# untitled.net
KiCad netlist of a schematic drawn in EAGLE
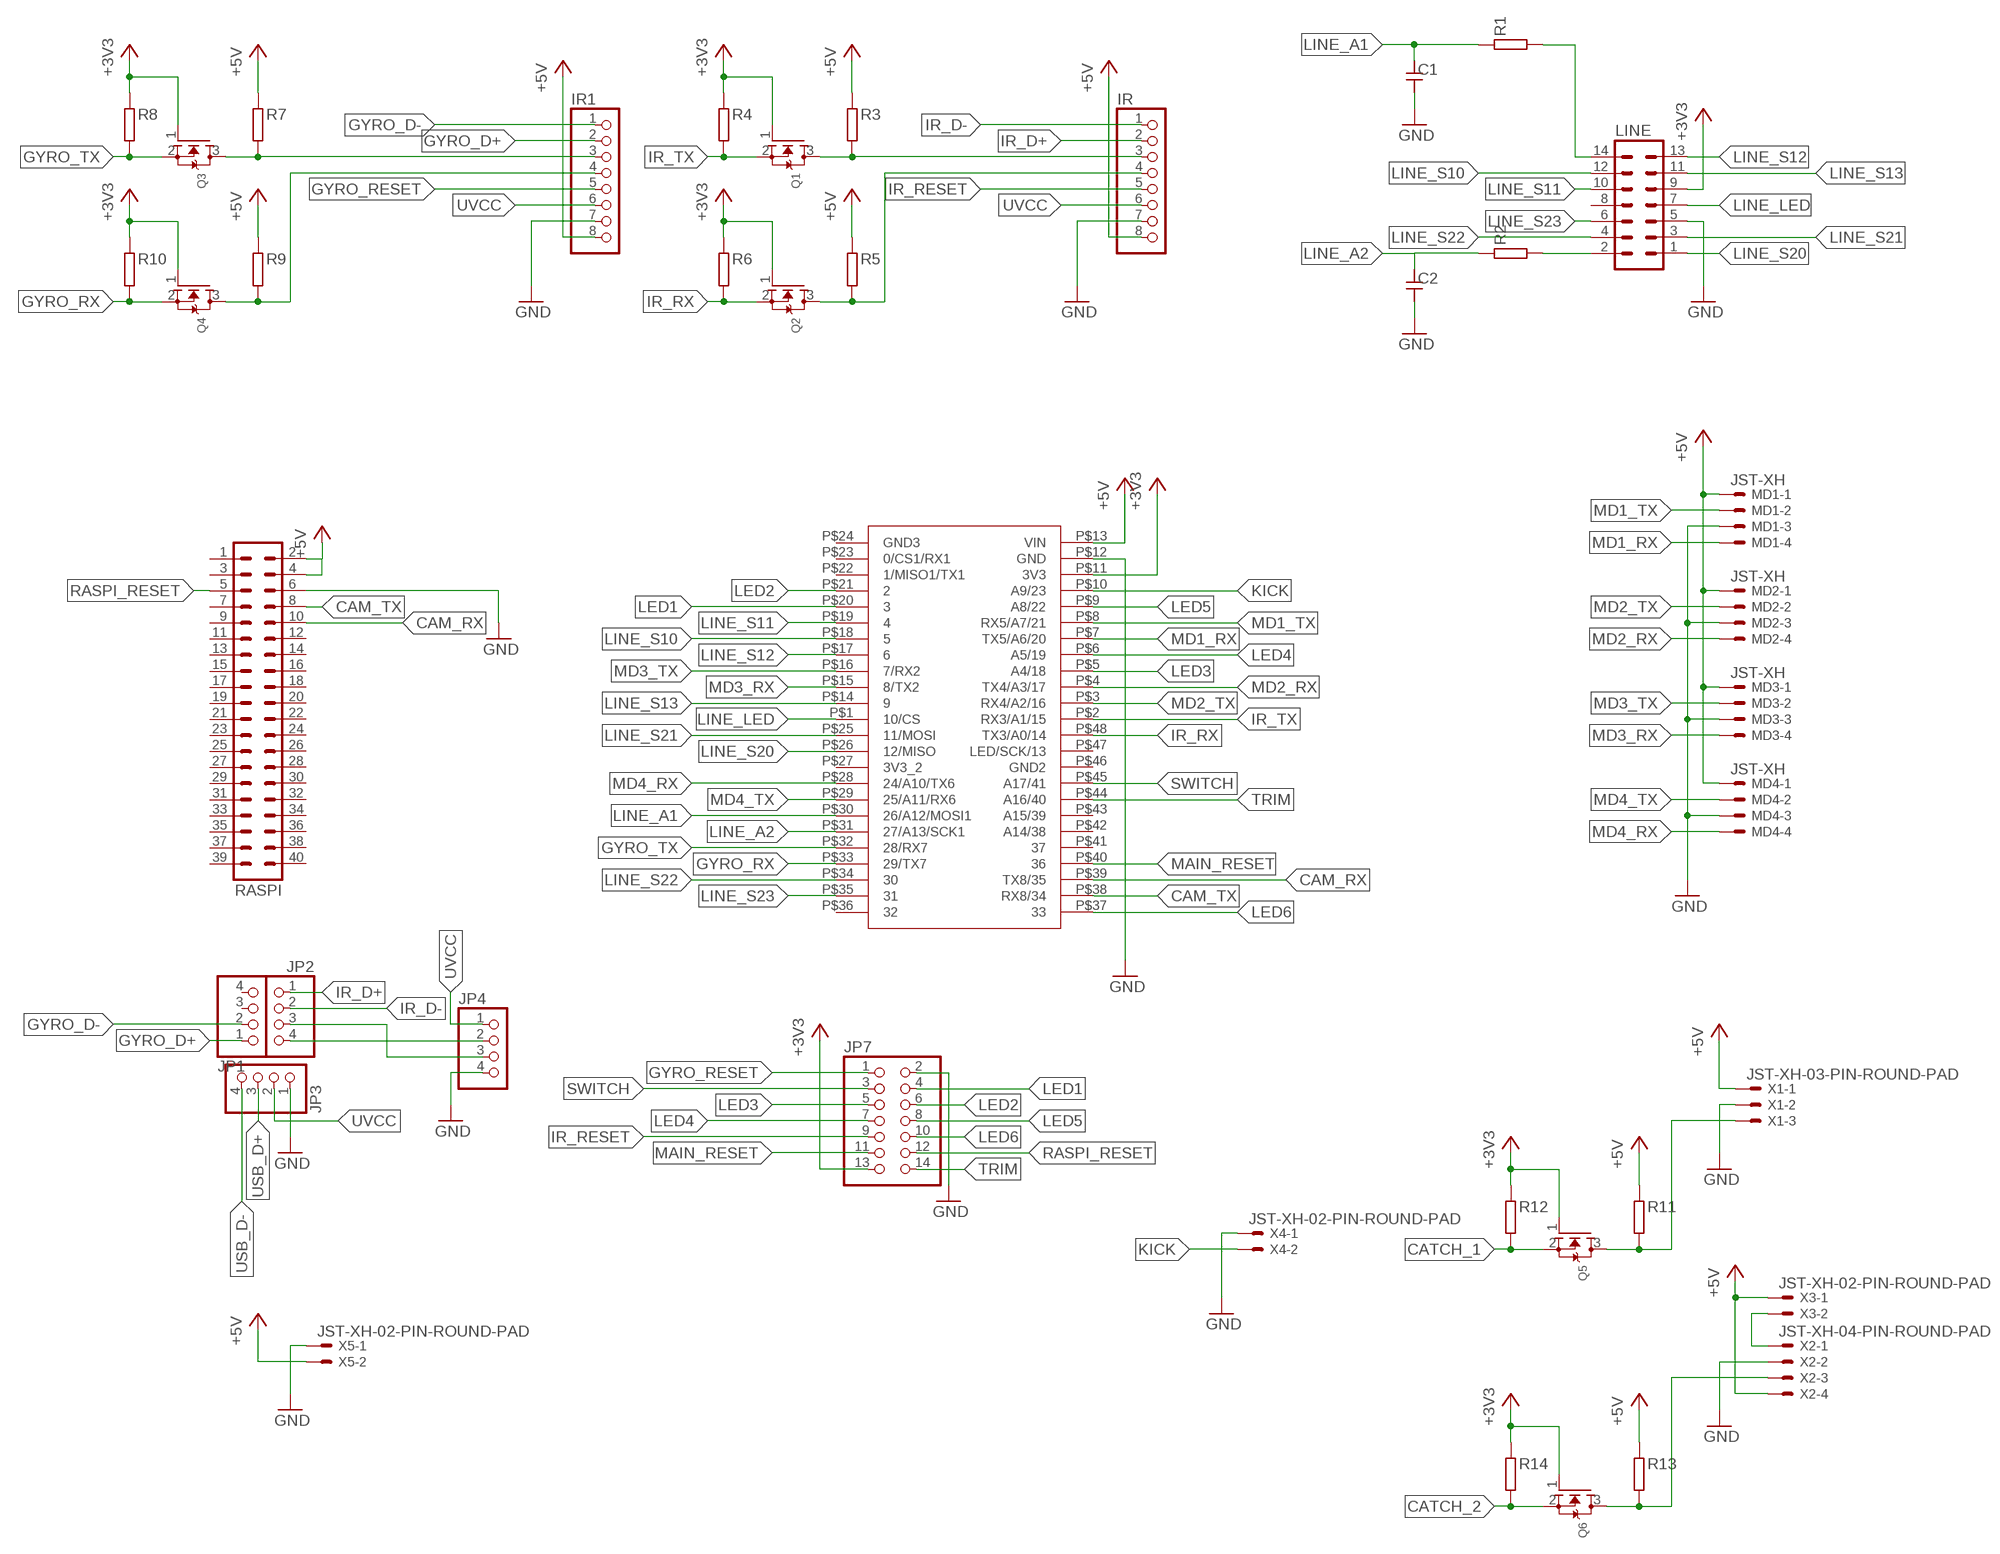
[diagram p0: schematic, sheet 1]

(export (version "E")
  (design (tool "Eeschema 10.0.6"))
  (components
    (comp (ref "C1")
      (value "CAPACITOR1608")
      (footprint "eagle-import:SMD1608")
      (libsource (lib "eagle-import") (part "CAPACITOR1608"))
    )
    (comp (ref "C2")
      (value "CAPACITOR1608")
      (footprint "eagle-import:SMD1608")
      (libsource (lib "eagle-import") (part "CAPACITOR1608"))
    )
    (comp (ref "IR")
      (value "PINHD-1X8")
      (footprint "eagle-import:1X08")
      (libsource (lib "eagle-import") (part "PINHD-1X8"))
    )
    (comp (ref "IR1")
      (value "PINHD-1X8")
      (footprint "eagle-import:1X08")
      (libsource (lib "eagle-import") (part "PINHD-1X8"))
    )
    (comp (ref "JP1")
      (value "PINHD-1X4")
      (footprint "eagle-import:1X04")
      (libsource (lib "eagle-import") (part "PINHD-1X4"))
    )
    (comp (ref "JP2")
      (value "PINHD-1X4")
      (footprint "eagle-import:1X04")
      (libsource (lib "eagle-import") (part "PINHD-1X4"))
    )
    (comp (ref "JP3")
      (value "PINHD-1X4")
      (footprint "eagle-import:1X04")
      (libsource (lib "eagle-import") (part "PINHD-1X4"))
    )
    (comp (ref "JP4")
      (value "PINHD-1X4")
      (footprint "eagle-import:1X04")
      (libsource (lib "eagle-import") (part "PINHD-1X4"))
    )
    (comp (ref "JP7")
      (value "PINHD-2X7")
      (footprint "eagle-import:2X07")
      (libsource (lib "eagle-import") (part "PINHD-2X7"))
    )
    (comp (ref "LINE")
      (value "MA07-2")
      (footprint "eagle-import:MA07-2")
      (libsource (lib "eagle-import") (part "MA07-2"))
    )
    (comp (ref "MD1")
      (value "JST-XH")
      (footprint "eagle-import:JST-XH-04-PACKAGE-ROUND-PAD")
      (libsource (lib "eagle-import") (part "JST-XH-04-PIN-ROUND-PAD"))
    )
    (comp (ref "MD2")
      (value "JST-XH")
      (footprint "eagle-import:JST-XH-04-PACKAGE-ROUND-PAD")
      (libsource (lib "eagle-import") (part "JST-XH-04-PIN-ROUND-PAD"))
    )
    (comp (ref "MD3")
      (value "JST-XH")
      (footprint "eagle-import:JST-XH-04-PACKAGE-ROUND-PAD")
      (libsource (lib "eagle-import") (part "JST-XH-04-PIN-ROUND-PAD"))
    )
    (comp (ref "MD4")
      (value "JST-XH")
      (footprint "eagle-import:JST-XH-04-PACKAGE-ROUND-PAD")
      (libsource (lib "eagle-import") (part "JST-XH-04-PIN-ROUND-PAD"))
    )
    (comp (ref "Q1")
      (value "MOSFET-NREFLOW")
      (footprint "eagle-import:SOT23")
      (libsource (lib "eagle-import") (part "MOSFET-NREFLOW"))
    )
    (comp (ref "Q2")
      (value "MOSFET-NREFLOW")
      (footprint "eagle-import:SOT23")
      (libsource (lib "eagle-import") (part "MOSFET-NREFLOW"))
    )
    (comp (ref "Q3")
      (value "MOSFET-NREFLOW")
      (footprint "eagle-import:SOT23")
      (libsource (lib "eagle-import") (part "MOSFET-NREFLOW"))
    )
    (comp (ref "Q4")
      (value "MOSFET-NREFLOW")
      (footprint "eagle-import:SOT23")
      (libsource (lib "eagle-import") (part "MOSFET-NREFLOW"))
    )
    (comp (ref "Q5")
      (value "MOSFET-NREFLOW")
      (footprint "eagle-import:SOT23")
      (libsource (lib "eagle-import") (part "MOSFET-NREFLOW"))
    )
    (comp (ref "Q6")
      (value "MOSFET-NREFLOW")
      (footprint "eagle-import:SOT23")
      (libsource (lib "eagle-import") (part "MOSFET-NREFLOW"))
    )
    (comp (ref "R1")
      (value "RESISTOR1608")
      (footprint "eagle-import:SMD1608")
      (libsource (lib "eagle-import") (part "RESISTOR1608"))
    )
    (comp (ref "R2")
      (value "RESISTOR1608")
      (footprint "eagle-import:SMD1608")
      (libsource (lib "eagle-import") (part "RESISTOR1608"))
    )
    (comp (ref "R3")
      (value "RESISTOR1608")
      (footprint "eagle-import:SMD1608")
      (libsource (lib "eagle-import") (part "RESISTOR1608"))
    )
    (comp (ref "R4")
      (value "RESISTOR1608")
      (footprint "eagle-import:SMD1608")
      (libsource (lib "eagle-import") (part "RESISTOR1608"))
    )
    (comp (ref "R5")
      (value "RESISTOR1608")
      (footprint "eagle-import:SMD1608")
      (libsource (lib "eagle-import") (part "RESISTOR1608"))
    )
    (comp (ref "R6")
      (value "RESISTOR1608")
      (footprint "eagle-import:SMD1608")
      (libsource (lib "eagle-import") (part "RESISTOR1608"))
    )
    (comp (ref "R7")
      (value "RESISTOR1608")
      (footprint "eagle-import:SMD1608")
      (libsource (lib "eagle-import") (part "RESISTOR1608"))
    )
    (comp (ref "R8")
      (value "RESISTOR1608")
      (footprint "eagle-import:SMD1608")
      (libsource (lib "eagle-import") (part "RESISTOR1608"))
    )
    (comp (ref "R9")
      (value "RESISTOR1608")
      (footprint "eagle-import:SMD1608")
      (libsource (lib "eagle-import") (part "RESISTOR1608"))
    )
    (comp (ref "R10")
      (value "RESISTOR1608")
      (footprint "eagle-import:SMD1608")
      (libsource (lib "eagle-import") (part "RESISTOR1608"))
    )
    (comp (ref "R11")
      (value "RESISTOR1608")
      (footprint "eagle-import:SMD1608")
      (libsource (lib "eagle-import") (part "RESISTOR1608"))
    )
    (comp (ref "R12")
      (value "RESISTOR1608")
      (footprint "eagle-import:SMD1608")
      (libsource (lib "eagle-import") (part "RESISTOR1608"))
    )
    (comp (ref "R13")
      (value "RESISTOR1608")
      (footprint "eagle-import:SMD1608")
      (libsource (lib "eagle-import") (part "RESISTOR1608"))
    )
    (comp (ref "R14")
      (value "RESISTOR1608")
      (footprint "eagle-import:SMD1608")
      (libsource (lib "eagle-import") (part "RESISTOR1608"))
    )
    (comp (ref "RASPI")
      (value "MA20-2")
      (footprint "eagle-import:MA20-2")
      (libsource (lib "eagle-import") (part "MA20-2"))
    )
    (comp (ref "U$1")
      (value "TEENSY4.1")
      (footprint "eagle-import:TEENSY4.1")
      (libsource (lib "eagle-import") (part "TEENSY4.1"))
    )
    (comp (ref "X1")
      (value "JST-XH-03-PIN-ROUND-PAD")
      (footprint "eagle-import:JST-XH-03-PACKAGE-ROUND-PAD")
      (libsource (lib "eagle-import") (part "JST-XH-03-PIN-ROUND-PAD"))
    )
    (comp (ref "X2")
      (value "JST-XH-04-PIN-ROUND-PAD")
      (footprint "eagle-import:JST-XH-04-PACKAGE-ROUND-PAD")
      (libsource (lib "eagle-import") (part "JST-XH-04-PIN-ROUND-PAD"))
    )
    (comp (ref "X3")
      (value "JST-XH-02-PIN-ROUND-PAD")
      (footprint "eagle-import:JST-XH-02-PACKAGE-ROUND-PAD")
      (libsource (lib "eagle-import") (part "JST-XH-02-PIN-ROUND-PAD"))
    )
    (comp (ref "X4")
      (value "JST-XH-02-PIN-ROUND-PAD")
      (footprint "eagle-import:JST-XH-02-PACKAGE-ROUND-PAD")
      (libsource (lib "eagle-import") (part "JST-XH-02-PIN-ROUND-PAD"))
    )
    (comp (ref "X5")
      (value "JST-XH-02-PIN-ROUND-PAD")
      (footprint "eagle-import:JST-XH-02-PACKAGE-ROUND-PAD")
      (libsource (lib "eagle-import") (part "JST-XH-02-PIN-ROUND-PAD"))
    )
  )
  (nets
    (net (code "1") (name "+3V3") (class "Default")
      (node (ref "JP7") (pin "13") (pinfunction "13_13") (pintype "passive"))
      (node (ref "LINE") (pin "9") (pinfunction "9_9") (pintype "passive"))
      (node (ref "Q1") (pin "1") (pinfunction "G_1") (pintype "bidirectional"))
      (node (ref "Q2") (pin "1") (pinfunction "G_1") (pintype "bidirectional"))
      (node (ref "Q3") (pin "1") (pinfunction "G_1") (pintype "bidirectional"))
      (node (ref "Q4") (pin "1") (pinfunction "G_1") (pintype "bidirectional"))
      (node (ref "Q5") (pin "1") (pinfunction "G_1") (pintype "bidirectional"))
      (node (ref "Q6") (pin "1") (pinfunction "G_1") (pintype "bidirectional"))
      (node (ref "R10") (pin "1") (pinfunction "1_1") (pintype "passive"))
      (node (ref "R12") (pin "1") (pinfunction "1_1") (pintype "passive"))
      (node (ref "R14") (pin "1") (pinfunction "1_1") (pintype "passive"))
      (node (ref "R4") (pin "1") (pinfunction "1_1") (pintype "passive"))
      (node (ref "R6") (pin "1") (pinfunction "1_1") (pintype "passive"))
      (node (ref "R8") (pin "1") (pinfunction "1_1") (pintype "passive"))
      (node (ref "U$1") (pin "P$11") (pinfunction "3V3_P$11") (pintype "bidirectional"))
    )
    (net (code "2") (name "+5V") (class "Default")
      (node (ref "IR") (pin "8") (pinfunction "8_8") (pintype "passive"))
      (node (ref "IR1") (pin "8") (pinfunction "8_8") (pintype "passive"))
      (node (ref "MD1") (pin "1") (pinfunction "S_1") (pintype "passive"))
      (node (ref "MD2") (pin "1") (pinfunction "S_1") (pintype "passive"))
      (node (ref "MD3") (pin "1") (pinfunction "S_1") (pintype "passive"))
      (node (ref "MD4") (pin "1") (pinfunction "S_1") (pintype "passive"))
      (node (ref "R11") (pin "1") (pinfunction "1_1") (pintype "passive"))
      (node (ref "R13") (pin "1") (pinfunction "1_1") (pintype "passive"))
      (node (ref "R3") (pin "1") (pinfunction "1_1") (pintype "passive"))
      (node (ref "R5") (pin "1") (pinfunction "1_1") (pintype "passive"))
      (node (ref "R7") (pin "1") (pinfunction "1_1") (pintype "passive"))
      (node (ref "R9") (pin "1") (pinfunction "1_1") (pintype "passive"))
      (node (ref "RASPI") (pin "2") (pinfunction "2_2") (pintype "passive"))
      (node (ref "RASPI") (pin "4") (pinfunction "4_4") (pintype "passive"))
      (node (ref "U$1") (pin "P$13") (pinfunction "VIN_P$13") (pintype "bidirectional"))
      (node (ref "X1") (pin "1") (pinfunction "S_1") (pintype "passive"))
      (node (ref "X2") (pin "4") (pinfunction "S_4") (pintype "passive"))
      (node (ref "X3") (pin "1") (pinfunction "S_1") (pintype "passive"))
      (node (ref "X5") (pin "2") (pinfunction "S_2") (pintype "passive"))
    )
    (net (code "3") (name "CAM_RX") (class "Default")
      (node (ref "RASPI") (pin "10") (pinfunction "10_10") (pintype "passive"))
      (node (ref "U$1") (pin "P$39") (pinfunction "TX8/35_P$39") (pintype "bidirectional"))
    )
    (net (code "4") (name "CAM_TX") (class "Default")
      (node (ref "RASPI") (pin "8") (pinfunction "8_8") (pintype "passive"))
      (node (ref "U$1") (pin "P$38") (pinfunction "RX8/34_P$38") (pintype "bidirectional"))
    )
    (net (code "5") (name "CATCH_1") (class "Default")
      (node (ref "Q5") (pin "2") (pinfunction "S_2") (pintype "bidirectional"))
      (node (ref "R12") (pin "2") (pinfunction "2_2") (pintype "passive"))
    )
    (net (code "6") (name "CATCH_2") (class "Default")
      (node (ref "Q6") (pin "2") (pinfunction "S_2") (pintype "bidirectional"))
      (node (ref "R14") (pin "2") (pinfunction "2_2") (pintype "passive"))
    )
    (net (code "7") (name "GND") (class "Default")
      (node (ref "C1") (pin "2") (pinfunction "2_2") (pintype "passive"))
      (node (ref "C2") (pin "2") (pinfunction "2_2") (pintype "passive"))
      (node (ref "IR") (pin "7") (pinfunction "7_7") (pintype "passive"))
      (node (ref "IR1") (pin "7") (pinfunction "7_7") (pintype "passive"))
      (node (ref "JP3") (pin "1") (pinfunction "1_1") (pintype "passive"))
      (node (ref "JP4") (pin "4") (pinfunction "4_4") (pintype "passive"))
      (node (ref "JP7") (pin "2") (pinfunction "2_2") (pintype "passive"))
      (node (ref "LINE") (pin "5") (pinfunction "5_5") (pintype "passive"))
      (node (ref "MD1") (pin "3") (pinfunction "S_3") (pintype "passive"))
      (node (ref "MD2") (pin "3") (pinfunction "S_3") (pintype "passive"))
      (node (ref "MD3") (pin "3") (pinfunction "S_3") (pintype "passive"))
      (node (ref "MD4") (pin "3") (pinfunction "S_3") (pintype "passive"))
      (node (ref "RASPI") (pin "6") (pinfunction "6_6") (pintype "passive"))
      (node (ref "U$1") (pin "P$12") (pinfunction "GND_P$12") (pintype "bidirectional"))
      (node (ref "X1") (pin "2") (pinfunction "S_2") (pintype "passive"))
      (node (ref "X2") (pin "2") (pinfunction "S_2") (pintype "passive"))
      (node (ref "X4") (pin "1") (pinfunction "S_1") (pintype "passive"))
      (node (ref "X5") (pin "1") (pinfunction "S_1") (pintype "passive"))
    )
    (net (code "8") (name "GYRO_D+") (class "Default")
      (node (ref "IR1") (pin "2") (pinfunction "2_2") (pintype "passive"))
      (node (ref "JP1") (pin "1") (pinfunction "1_1") (pintype "passive"))
    )
    (net (code "9") (name "GYRO_D-") (class "Default")
      (node (ref "IR1") (pin "1") (pinfunction "1_1") (pintype "passive"))
      (node (ref "JP1") (pin "2") (pinfunction "2_2") (pintype "passive"))
    )
    (net (code "10") (name "GYRO_RESET") (class "Default")
      (node (ref "IR1") (pin "5") (pinfunction "5_5") (pintype "passive"))
      (node (ref "JP7") (pin "1") (pinfunction "1_1") (pintype "passive"))
    )
    (net (code "11") (name "GYRO_RX") (class "Default")
      (node (ref "Q4") (pin "2") (pinfunction "S_2") (pintype "bidirectional"))
      (node (ref "R10") (pin "2") (pinfunction "2_2") (pintype "passive"))
      (node (ref "U$1") (pin "P$33") (pinfunction "29/TX7_P$33") (pintype "bidirectional"))
    )
    (net (code "12") (name "GYRO_TX") (class "Default")
      (node (ref "Q3") (pin "2") (pinfunction "S_2") (pintype "bidirectional"))
      (node (ref "R8") (pin "2") (pinfunction "2_2") (pintype "passive"))
      (node (ref "U$1") (pin "P$32") (pinfunction "28/RX7_P$32") (pintype "bidirectional"))
    )
    (net (code "13") (name "IR_D+") (class "Default")
      (node (ref "IR") (pin "2") (pinfunction "2_2") (pintype "passive"))
      (node (ref "JP2") (pin "1") (pinfunction "1_1") (pintype "passive"))
    )
    (net (code "14") (name "IR_D-") (class "Default")
      (node (ref "IR") (pin "1") (pinfunction "1_1") (pintype "passive"))
      (node (ref "JP2") (pin "2") (pinfunction "2_2") (pintype "passive"))
    )
    (net (code "15") (name "IR_RESET") (class "Default")
      (node (ref "IR") (pin "5") (pinfunction "5_5") (pintype "passive"))
      (node (ref "JP7") (pin "9") (pinfunction "9_9") (pintype "passive"))
    )
    (net (code "16") (name "IR_RX") (class "Default")
      (node (ref "Q2") (pin "2") (pinfunction "S_2") (pintype "bidirectional"))
      (node (ref "R6") (pin "2") (pinfunction "2_2") (pintype "passive"))
      (node (ref "U$1") (pin "P$48") (pinfunction "TX3/A0/14_P$48") (pintype "bidirectional"))
    )
    (net (code "17") (name "IR_TX") (class "Default")
      (node (ref "Q1") (pin "2") (pinfunction "S_2") (pintype "bidirectional"))
      (node (ref "R4") (pin "2") (pinfunction "2_2") (pintype "passive"))
      (node (ref "U$1") (pin "P$2") (pinfunction "RX3/A1/15_P$2") (pintype "bidirectional"))
    )
    (net (code "18") (name "KICK") (class "Default")
      (node (ref "U$1") (pin "P$10") (pinfunction "A9/23_P$10") (pintype "bidirectional"))
      (node (ref "X4") (pin "2") (pinfunction "S_2") (pintype "passive"))
    )
    (net (code "19") (name "LED1") (class "Default")
      (node (ref "JP7") (pin "4") (pinfunction "4_4") (pintype "passive"))
      (node (ref "U$1") (pin "P$20") (pinfunction "3_P$20") (pintype "bidirectional"))
    )
    (net (code "20") (name "LED2") (class "Default")
      (node (ref "JP7") (pin "6") (pinfunction "6_6") (pintype "passive"))
      (node (ref "U$1") (pin "P$21") (pinfunction "2_P$21") (pintype "bidirectional"))
    )
    (net (code "21") (name "LED3") (class "Default")
      (node (ref "JP7") (pin "5") (pinfunction "5_5") (pintype "passive"))
      (node (ref "U$1") (pin "P$5") (pinfunction "A4/18_P$5") (pintype "bidirectional"))
    )
    (net (code "22") (name "LED4") (class "Default")
      (node (ref "JP7") (pin "7") (pinfunction "7_7") (pintype "passive"))
      (node (ref "U$1") (pin "P$6") (pinfunction "A5/19_P$6") (pintype "bidirectional"))
    )
    (net (code "23") (name "LED5") (class "Default")
      (node (ref "JP7") (pin "8") (pinfunction "8_8") (pintype "passive"))
      (node (ref "U$1") (pin "P$9") (pinfunction "A8/22_P$9") (pintype "bidirectional"))
    )
    (net (code "24") (name "LED6") (class "Default")
      (node (ref "JP7") (pin "10") (pinfunction "10_10") (pintype "passive"))
      (node (ref "U$1") (pin "P$37") (pinfunction "33_P$37") (pintype "bidirectional"))
    )
    (net (code "25") (name "LINE_A1") (class "Default")
      (node (ref "C1") (pin "1") (pinfunction "1_1") (pintype "passive"))
      (node (ref "R1") (pin "1") (pinfunction "1_1") (pintype "passive"))
      (node (ref "U$1") (pin "P$30") (pinfunction "26/A12/MOSI1_P$30") (pintype "bidirectional"))
    )
    (net (code "26") (name "LINE_A2") (class "Default")
      (node (ref "C2") (pin "1") (pinfunction "1_1") (pintype "passive"))
      (node (ref "R2") (pin "1") (pinfunction "1_1") (pintype "passive"))
      (node (ref "U$1") (pin "P$31") (pinfunction "27/A13/SCK1_P$31") (pintype "bidirectional"))
    )
    (net (code "27") (name "LINE_LED") (class "Default")
      (node (ref "LINE") (pin "7") (pinfunction "7_7") (pintype "passive"))
      (node (ref "U$1") (pin "P$1") (pinfunction "10/CS_P$1") (pintype "bidirectional"))
    )
    (net (code "28") (name "LINE_S10") (class "Default")
      (node (ref "LINE") (pin "12") (pinfunction "12_12") (pintype "passive"))
      (node (ref "U$1") (pin "P$18") (pinfunction "5_P$18") (pintype "bidirectional"))
    )
    (net (code "29") (name "LINE_S11") (class "Default")
      (node (ref "LINE") (pin "10") (pinfunction "10_10") (pintype "passive"))
      (node (ref "U$1") (pin "P$19") (pinfunction "4_P$19") (pintype "bidirectional"))
    )
    (net (code "30") (name "LINE_S12") (class "Default")
      (node (ref "LINE") (pin "13") (pinfunction "13_13") (pintype "passive"))
      (node (ref "U$1") (pin "P$17") (pinfunction "6_P$17") (pintype "bidirectional"))
    )
    (net (code "31") (name "LINE_S13") (class "Default")
      (node (ref "LINE") (pin "11") (pinfunction "11_11") (pintype "passive"))
      (node (ref "U$1") (pin "P$14") (pinfunction "9_P$14") (pintype "bidirectional"))
    )
    (net (code "32") (name "LINE_S20") (class "Default")
      (node (ref "LINE") (pin "1") (pinfunction "1_1") (pintype "passive"))
      (node (ref "U$1") (pin "P$26") (pinfunction "12/MISO_P$26") (pintype "bidirectional"))
    )
    (net (code "33") (name "LINE_S21") (class "Default")
      (node (ref "LINE") (pin "3") (pinfunction "3_3") (pintype "passive"))
      (node (ref "U$1") (pin "P$25") (pinfunction "11/MOSI_P$25") (pintype "bidirectional"))
    )
    (net (code "34") (name "LINE_S22") (class "Default")
      (node (ref "LINE") (pin "4") (pinfunction "4_4") (pintype "passive"))
      (node (ref "U$1") (pin "P$34") (pinfunction "30_P$34") (pintype "bidirectional"))
    )
    (net (code "35") (name "LINE_S23") (class "Default")
      (node (ref "LINE") (pin "6") (pinfunction "6_6") (pintype "passive"))
      (node (ref "U$1") (pin "P$35") (pinfunction "31_P$35") (pintype "bidirectional"))
    )
    (net (code "36") (name "MAIN_RESET") (class "Default")
      (node (ref "JP7") (pin "11") (pinfunction "11_11") (pintype "passive"))
      (node (ref "U$1") (pin "P$40") (pinfunction "36_P$40") (pintype "bidirectional"))
    )
    (net (code "37") (name "MD1_RX") (class "Default")
      (node (ref "MD1") (pin "4") (pinfunction "S_4") (pintype "passive"))
      (node (ref "U$1") (pin "P$7") (pinfunction "TX5/A6/20_P$7") (pintype "bidirectional"))
    )
    (net (code "38") (name "MD1_TX") (class "Default")
      (node (ref "MD1") (pin "2") (pinfunction "S_2") (pintype "passive"))
      (node (ref "U$1") (pin "P$8") (pinfunction "RX5/A7/21_P$8") (pintype "bidirectional"))
    )
    (net (code "39") (name "MD2_RX") (class "Default")
      (node (ref "MD2") (pin "4") (pinfunction "S_4") (pintype "passive"))
      (node (ref "U$1") (pin "P$4") (pinfunction "TX4/A3/17_P$4") (pintype "bidirectional"))
    )
    (net (code "40") (name "MD2_TX") (class "Default")
      (node (ref "MD2") (pin "2") (pinfunction "S_2") (pintype "passive"))
      (node (ref "U$1") (pin "P$3") (pinfunction "RX4/A2/16_P$3") (pintype "bidirectional"))
    )
    (net (code "41") (name "MD3_RX") (class "Default")
      (node (ref "MD3") (pin "4") (pinfunction "S_4") (pintype "passive"))
      (node (ref "U$1") (pin "P$15") (pinfunction "8/TX2_P$15") (pintype "bidirectional"))
    )
    (net (code "42") (name "MD3_TX") (class "Default")
      (node (ref "MD3") (pin "2") (pinfunction "S_2") (pintype "passive"))
      (node (ref "U$1") (pin "P$16") (pinfunction "7/RX2_P$16") (pintype "bidirectional"))
    )
    (net (code "43") (name "MD4_RX") (class "Default")
      (node (ref "MD4") (pin "4") (pinfunction "S_4") (pintype "passive"))
      (node (ref "U$1") (pin "P$28") (pinfunction "24/A10/TX6_P$28") (pintype "bidirectional"))
    )
    (net (code "44") (name "MD4_TX") (class "Default")
      (node (ref "MD4") (pin "2") (pinfunction "S_2") (pintype "passive"))
      (node (ref "U$1") (pin "P$29") (pinfunction "25/A11/RX6_P$29") (pintype "bidirectional"))
    )
    (net (code "45") (name "Net-(JP2-Pad3)") (class "Default")
      (node (ref "JP2") (pin "3") (pinfunction "3_3") (pintype "passive"))
      (node (ref "JP4") (pin "3") (pinfunction "3_3") (pintype "passive"))
    )
    (net (code "46") (name "Net-(JP2-Pad4)") (class "Default")
      (node (ref "JP2") (pin "4") (pinfunction "4_4") (pintype "passive"))
      (node (ref "JP4") (pin "2") (pinfunction "2_2") (pintype "passive"))
    )
    (net (code "47") (name "Net-(LINE-Pad2)") (class "Default")
      (node (ref "LINE") (pin "2") (pinfunction "2_2") (pintype "passive"))
      (node (ref "R2") (pin "2") (pinfunction "2_2") (pintype "passive"))
    )
    (net (code "48") (name "Net-(LINE-Pad14)") (class "Default")
      (node (ref "LINE") (pin "14") (pinfunction "14_14") (pintype "passive"))
      (node (ref "R1") (pin "2") (pinfunction "2_2") (pintype "passive"))
    )
    (net (code "49") (name "Net-(Q1-D)") (class "Default")
      (node (ref "IR") (pin "3") (pinfunction "3_3") (pintype "passive"))
      (node (ref "Q1") (pin "3") (pinfunction "D_3") (pintype "bidirectional"))
      (node (ref "R3") (pin "2") (pinfunction "2_2") (pintype "passive"))
    )
    (net (code "50") (name "Net-(Q2-D)") (class "Default")
      (node (ref "IR") (pin "4") (pinfunction "4_4") (pintype "passive"))
      (node (ref "Q2") (pin "3") (pinfunction "D_3") (pintype "bidirectional"))
      (node (ref "R5") (pin "2") (pinfunction "2_2") (pintype "passive"))
    )
    (net (code "51") (name "Net-(Q3-D)") (class "Default")
      (node (ref "IR1") (pin "3") (pinfunction "3_3") (pintype "passive"))
      (node (ref "Q3") (pin "3") (pinfunction "D_3") (pintype "bidirectional"))
      (node (ref "R7") (pin "2") (pinfunction "2_2") (pintype "passive"))
    )
    (net (code "52") (name "Net-(Q4-D)") (class "Default")
      (node (ref "IR1") (pin "4") (pinfunction "4_4") (pintype "passive"))
      (node (ref "Q4") (pin "3") (pinfunction "D_3") (pintype "bidirectional"))
      (node (ref "R9") (pin "2") (pinfunction "2_2") (pintype "passive"))
    )
    (net (code "53") (name "Net-(Q5-D)") (class "Default")
      (node (ref "Q5") (pin "3") (pinfunction "D_3") (pintype "bidirectional"))
      (node (ref "R11") (pin "2") (pinfunction "2_2") (pintype "passive"))
      (node (ref "X1") (pin "3") (pinfunction "S_3") (pintype "passive"))
    )
    (net (code "54") (name "Net-(Q6-D)") (class "Default")
      (node (ref "Q6") (pin "3") (pinfunction "D_3") (pintype "bidirectional"))
      (node (ref "R13") (pin "2") (pinfunction "2_2") (pintype "passive"))
      (node (ref "X2") (pin "3") (pinfunction "S_3") (pintype "passive"))
    )
    (net (code "55") (name "Net-(X2A-S)") (class "Default")
      (node (ref "X2") (pin "1") (pinfunction "S_1") (pintype "passive"))
      (node (ref "X3") (pin "2") (pinfunction "S_2") (pintype "passive"))
    )
    (net (code "56") (name "RASPI_RESET") (class "Default")
      (node (ref "JP7") (pin "12") (pinfunction "12_12") (pintype "passive"))
      (node (ref "RASPI") (pin "5") (pinfunction "5_5") (pintype "passive"))
    )
    (net (code "57") (name "SWITCH") (class "Default")
      (node (ref "JP7") (pin "3") (pinfunction "3_3") (pintype "passive"))
      (node (ref "U$1") (pin "P$45") (pinfunction "A17/41_P$45") (pintype "bidirectional"))
    )
    (net (code "58") (name "TRIM") (class "Default")
      (node (ref "JP7") (pin "14") (pinfunction "14_14") (pintype "passive"))
      (node (ref "U$1") (pin "P$44") (pinfunction "A16/40_P$44") (pintype "bidirectional"))
    )
    (net (code "59") (name "USB_D+") (class "Default")
      (node (ref "JP3") (pin "3") (pinfunction "3_3") (pintype "passive"))
    )
    (net (code "60") (name "USB_D-") (class "Default")
      (node (ref "JP3") (pin "4") (pinfunction "4_4") (pintype "passive"))
    )
    (net (code "61") (name "UVCC") (class "Default")
      (node (ref "IR") (pin "6") (pinfunction "6_6") (pintype "passive"))
      (node (ref "IR1") (pin "6") (pinfunction "6_6") (pintype "passive"))
      (node (ref "JP3") (pin "2") (pinfunction "2_2") (pintype "passive"))
      (node (ref "JP4") (pin "1") (pinfunction "1_1") (pintype "passive"))
    )
    (net (code "62") (name "unconnected-(JP1-Pad3)") (class "Default")
      (node (ref "JP1") (pin "3") (pinfunction "3_3") (pintype "passive"))
    )
    (net (code "63") (name "unconnected-(JP1-Pad4)") (class "Default")
      (node (ref "JP1") (pin "4") (pinfunction "4_4") (pintype "passive"))
    )
    (net (code "64") (name "unconnected-(LINE-Pad8)") (class "Default")
      (node (ref "LINE") (pin "8") (pinfunction "8_8") (pintype "passive"))
    )
    (net (code "65") (name "unconnected-(RASPI-Pad1)") (class "Default")
      (node (ref "RASPI") (pin "1") (pinfunction "1_1") (pintype "passive"))
    )
    (net (code "66") (name "unconnected-(RASPI-Pad3)") (class "Default")
      (node (ref "RASPI") (pin "3") (pinfunction "3_3") (pintype "passive"))
    )
    (net (code "67") (name "unconnected-(RASPI-Pad7)") (class "Default")
      (node (ref "RASPI") (pin "7") (pinfunction "7_7") (pintype "passive"))
    )
    (net (code "68") (name "unconnected-(RASPI-Pad9)") (class "Default")
      (node (ref "RASPI") (pin "9") (pinfunction "9_9") (pintype "passive"))
    )
    (net (code "69") (name "unconnected-(RASPI-Pad11)") (class "Default")
      (node (ref "RASPI") (pin "11") (pinfunction "11_11") (pintype "passive"))
    )
    (net (code "70") (name "unconnected-(RASPI-Pad12)") (class "Default")
      (node (ref "RASPI") (pin "12") (pinfunction "12_12") (pintype "passive"))
    )
    (net (code "71") (name "unconnected-(RASPI-Pad13)") (class "Default")
      (node (ref "RASPI") (pin "13") (pinfunction "13_13") (pintype "passive"))
    )
    (net (code "72") (name "unconnected-(RASPI-Pad14)") (class "Default")
      (node (ref "RASPI") (pin "14") (pinfunction "14_14") (pintype "passive"))
    )
    (net (code "73") (name "unconnected-(RASPI-Pad15)") (class "Default")
      (node (ref "RASPI") (pin "15") (pinfunction "15_15") (pintype "passive"))
    )
    (net (code "74") (name "unconnected-(RASPI-Pad16)") (class "Default")
      (node (ref "RASPI") (pin "16") (pinfunction "16_16") (pintype "passive"))
    )
    (net (code "75") (name "unconnected-(RASPI-Pad17)") (class "Default")
      (node (ref "RASPI") (pin "17") (pinfunction "17_17") (pintype "passive"))
    )
    (net (code "76") (name "unconnected-(RASPI-Pad18)") (class "Default")
      (node (ref "RASPI") (pin "18") (pinfunction "18_18") (pintype "passive"))
    )
    (net (code "77") (name "unconnected-(RASPI-Pad19)") (class "Default")
      (node (ref "RASPI") (pin "19") (pinfunction "19_19") (pintype "passive"))
    )
    (net (code "78") (name "unconnected-(RASPI-Pad20)") (class "Default")
      (node (ref "RASPI") (pin "20") (pinfunction "20_20") (pintype "passive"))
    )
    (net (code "79") (name "unconnected-(RASPI-Pad21)") (class "Default")
      (node (ref "RASPI") (pin "21") (pinfunction "21_21") (pintype "passive"))
    )
    (net (code "80") (name "unconnected-(RASPI-Pad22)") (class "Default")
      (node (ref "RASPI") (pin "22") (pinfunction "22_22") (pintype "passive"))
    )
    (net (code "81") (name "unconnected-(RASPI-Pad23)") (class "Default")
      (node (ref "RASPI") (pin "23") (pinfunction "23_23") (pintype "passive"))
    )
    (net (code "82") (name "unconnected-(RASPI-Pad24)") (class "Default")
      (node (ref "RASPI") (pin "24") (pinfunction "24_24") (pintype "passive"))
    )
    (net (code "83") (name "unconnected-(RASPI-Pad25)") (class "Default")
      (node (ref "RASPI") (pin "25") (pinfunction "25_25") (pintype "passive"))
    )
    (net (code "84") (name "unconnected-(RASPI-Pad26)") (class "Default")
      (node (ref "RASPI") (pin "26") (pinfunction "26_26") (pintype "passive"))
    )
    (net (code "85") (name "unconnected-(RASPI-Pad27)") (class "Default")
      (node (ref "RASPI") (pin "27") (pinfunction "27_27") (pintype "passive"))
    )
    (net (code "86") (name "unconnected-(RASPI-Pad28)") (class "Default")
      (node (ref "RASPI") (pin "28") (pinfunction "28_28") (pintype "passive"))
    )
    (net (code "87") (name "unconnected-(RASPI-Pad29)") (class "Default")
      (node (ref "RASPI") (pin "29") (pinfunction "29_29") (pintype "passive"))
    )
    (net (code "88") (name "unconnected-(RASPI-Pad30)") (class "Default")
      (node (ref "RASPI") (pin "30") (pinfunction "30_30") (pintype "passive"))
    )
    (net (code "89") (name "unconnected-(RASPI-Pad31)") (class "Default")
      (node (ref "RASPI") (pin "31") (pinfunction "31_31") (pintype "passive"))
    )
    (net (code "90") (name "unconnected-(RASPI-Pad32)") (class "Default")
      (node (ref "RASPI") (pin "32") (pinfunction "32_32") (pintype "passive"))
    )
    (net (code "91") (name "unconnected-(RASPI-Pad33)") (class "Default")
      (node (ref "RASPI") (pin "33") (pinfunction "33_33") (pintype "passive"))
    )
    (net (code "92") (name "unconnected-(RASPI-Pad34)") (class "Default")
      (node (ref "RASPI") (pin "34") (pinfunction "34_34") (pintype "passive"))
    )
    (net (code "93") (name "unconnected-(RASPI-Pad35)") (class "Default")
      (node (ref "RASPI") (pin "35") (pinfunction "35_35") (pintype "passive"))
    )
    (net (code "94") (name "unconnected-(RASPI-Pad36)") (class "Default")
      (node (ref "RASPI") (pin "36") (pinfunction "36_36") (pintype "passive"))
    )
    (net (code "95") (name "unconnected-(RASPI-Pad37)") (class "Default")
      (node (ref "RASPI") (pin "37") (pinfunction "37_37") (pintype "passive"))
    )
    (net (code "96") (name "unconnected-(RASPI-Pad38)") (class "Default")
      (node (ref "RASPI") (pin "38") (pinfunction "38_38") (pintype "passive"))
    )
    (net (code "97") (name "unconnected-(RASPI-Pad39)") (class "Default")
      (node (ref "RASPI") (pin "39") (pinfunction "39_39") (pintype "passive"))
    )
    (net (code "98") (name "unconnected-(RASPI-Pad40)") (class "Default")
      (node (ref "RASPI") (pin "40") (pinfunction "40_40") (pintype "passive"))
    )
    (net (code "99") (name "unconnected-(U$1-0{slash}CS1{slash}RX1-PadP$23)") (class "Default")
      (node (ref "U$1") (pin "P$23") (pinfunction "0/CS1/RX1_P$23") (pintype "bidirectional"))
    )
    (net (code "100") (name "unconnected-(U$1-1{slash}MISO1{slash}TX1-PadP$22)") (class "Default")
      (node (ref "U$1") (pin "P$22") (pinfunction "1/MISO1/TX1_P$22") (pintype "bidirectional"))
    )
    (net (code "101") (name "unconnected-(U$1-3V3_2-PadP$27)") (class "Default")
      (node (ref "U$1") (pin "P$27") (pinfunction "3V3_2_P$27") (pintype "bidirectional"))
    )
    (net (code "102") (name "unconnected-(U$1-32-PadP$36)") (class "Default")
      (node (ref "U$1") (pin "P$36") (pinfunction "32_P$36") (pintype "bidirectional"))
    )
    (net (code "103") (name "unconnected-(U$1-37-PadP$41)") (class "Default")
      (node (ref "U$1") (pin "P$41") (pinfunction "37_P$41") (pintype "bidirectional"))
    )
    (net (code "104") (name "unconnected-(U$1-A14{slash}38-PadP$42)") (class "Default")
      (node (ref "U$1") (pin "P$42") (pinfunction "A14/38_P$42") (pintype "bidirectional"))
    )
    (net (code "105") (name "unconnected-(U$1-A15{slash}39-PadP$43)") (class "Default")
      (node (ref "U$1") (pin "P$43") (pinfunction "A15/39_P$43") (pintype "bidirectional"))
    )
    (net (code "106") (name "unconnected-(U$1-GND2-PadP$46)") (class "Default")
      (node (ref "U$1") (pin "P$46") (pinfunction "GND2_P$46") (pintype "bidirectional"))
    )
    (net (code "107") (name "unconnected-(U$1-GND3-PadP$24)") (class "Default")
      (node (ref "U$1") (pin "P$24") (pinfunction "GND3_P$24") (pintype "bidirectional"))
    )
    (net (code "108") (name "unconnected-(U$1-LED{slash}SCK{slash}13-PadP$47)") (class "Default")
      (node (ref "U$1") (pin "P$47") (pinfunction "LED/SCK/13_P$47") (pintype "bidirectional"))
    )
  )
)
